# LM2596_Adjustable_AMS1117.net
KiCad netlist of a schematic drawn in Altium Designer
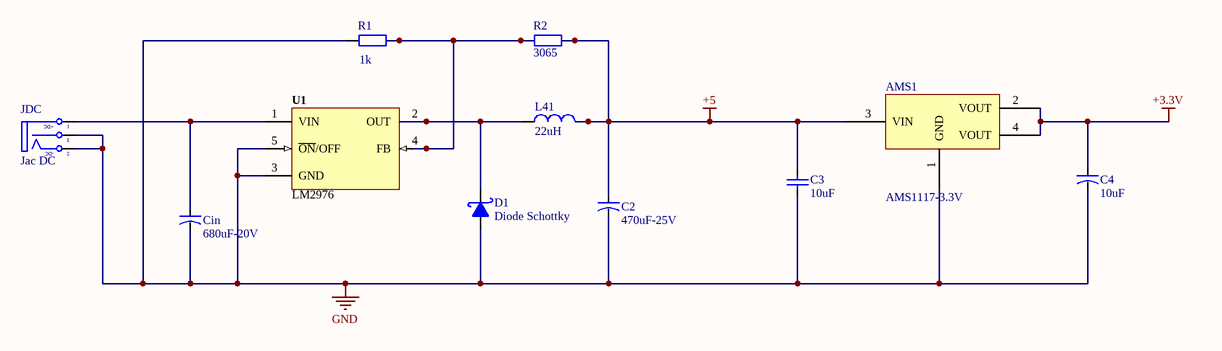
[diagram p0: LM2596 Adjustable_AMS1117.SchDoc]

(export (version "E")
  (design (tool "Eeschema 10.0.6"))
  (components
    (comp (ref "AMS1")
      (value "AMS1117-3.3V")
      (footprint "SOT223")
      (description "Dán")
      (libsource (lib "Altium_Lib_by_KhueNguyenCreator") (part "AMS1117 SMD"))
    )
    (comp (ref "C2")
      (value "470uF-25V")
      (footprint "CAP_D16")
      (description "Capacitor (Semiconductor SIM Model)")
      (fields (field (name "PUBLISHER") "Altium Limited"))
      (libsource (lib "My Library") (part "CAP-ALU-DIP"))
    )
    (comp (ref "C3")
      (value "10uF")
      (footprint "CAP_0805")
      (description "Capacitor")
      (fields (field (name "PUBLISHER") "Altium Limited"))
      (libsource (lib "My Library") (part "CapSMD"))
    )
    (comp (ref "C4")
      (value "10uF")
      (footprint "CAP_D16")
      (description "Capacitor (Semiconductor SIM Model)")
      (fields (field (name "PUBLISHER") "Altium Limited"))
      (libsource (lib "My Library") (part "CAP-ALU-DIP"))
    )
    (comp (ref "Cin")
      (value "680uF-20V")
      (footprint "CAP_D16")
      (description "Capacitor (Semiconductor SIM Model)")
      (fields (field (name "PUBLISHER") "Altium Limited"))
      (libsource (lib "My Library") (part "CAP-ALU-DIP"))
    )
    (comp (ref "D1")
      (value "Diode Schottky")
      (footprint "DIODE_ZENER_SMD")
      (description "Generic Diode Schottky")
      (libsource (lib "My Library") (part "Diode Schottky"))
    )
    (comp (ref "JDC")
      (value "Jac DC")
      (footprint "DC-IN")
      (description "Jac DC input")
      (libsource (lib "My Library") (part "DCIN"))
    )
    (comp (ref "L41")
      (value "22uH")
      (footprint "Inductor_SMD")
      (description "Inductor")
      (libsource (lib "My Library") (part "L1"))
    )
    (comp (ref "R1")
      (value "1k")
      (footprint "RES-SMD-0805")
      (description "Resistor SMD")
      (fields
        (field (name "MANUFACTURER") "Generic Components")
        (field (name "PUBLISHER") "Altium Hobart Technology Centre")
      )
      (libsource (lib "My Library") (part "Resistor - SMD"))
    )
    (comp (ref "R2")
      (value "3065")
      (footprint "RES_SMD_0805")
      (description "Resistor SMD")
      (fields
        (field (name "MANUFACTURER") "Generic Components")
        (field (name "PUBLISHER") "Altium Hobart Technology Centre")
      )
      (libsource (lib "My Library") (part "Resistor - SMD"))
    )
    (comp (ref "U1") (value "LM2976") (footprint "LM2576t") (libsource (lib "My Library") (part "LM2596")))
  )
  (nets
    (net (code "1") (name "+3.3V") (class "Default")
      (node (ref "AMS1") (pin "2") (pinfunction "VOUT_2") (pintype "passive"))
      (node (ref "AMS1") (pin "4") (pinfunction "VOUT_4") (pintype "passive"))
      (node (ref "C4") (pin "1") (pinfunction "1_1") (pintype "passive"))
    )
    (net (code "2") (name "+5") (class "Default")
      (node (ref "AMS1") (pin "3") (pinfunction "VIN_3") (pintype "passive"))
      (node (ref "C2") (pin "1") (pinfunction "1_1") (pintype "passive"))
      (node (ref "C3") (pin "2") (pinfunction "2_2") (pintype "passive"))
      (node (ref "L41") (pin "2") (pinfunction "2_2") (pintype "passive"))
      (node (ref "R2") (pin "1") (pinfunction "1_1") (pintype "passive"))
    )
    (net (code "3") (name "GND") (class "Default")
      (node (ref "AMS1") (pin "1") (pinfunction "GND_1") (pintype "passive"))
      (node (ref "C2") (pin "2") (pinfunction "2_2") (pintype "passive"))
      (node (ref "C3") (pin "1") (pinfunction "1_1") (pintype "passive"))
      (node (ref "C4") (pin "2") (pinfunction "2_2") (pintype "passive"))
      (node (ref "Cin") (pin "2") (pinfunction "2_2") (pintype "passive"))
      (node (ref "D1") (pin "1") (pinfunction "A_1") (pintype "passive"))
      (node (ref "JDC") (pin "2") (pinfunction "TN_2") (pintype "passive"))
      (node (ref "JDC") (pin "3") (pinfunction "S_3") (pintype "power_in"))
      (node (ref "R1") (pin "2") (pinfunction "2_2") (pintype "passive"))
      (node (ref "U1") (pin "3") (pinfunction "GND_3") (pintype "power_in"))
      (node (ref "U1") (pin "5") (pinfunction "~{ON}/OFF_5") (pintype "input"))
    )
    (net (code "4") (name "Net-(D1-K)") (class "Default")
      (node (ref "D1") (pin "2") (pinfunction "K_2") (pintype "passive"))
      (node (ref "L41") (pin "1") (pinfunction "1_1") (pintype "passive"))
      (node (ref "U1") (pin "2") (pinfunction "OUT_2") (pintype "power_in"))
    )
    (net (code "5") (name "Net-(JDC-T)") (class "Default")
      (node (ref "Cin") (pin "1") (pinfunction "1_1") (pintype "passive"))
      (node (ref "JDC") (pin "1") (pinfunction "T_1") (pintype "passive"))
      (node (ref "U1") (pin "1") (pinfunction "VIN_1") (pintype "power_in"))
    )
    (net (code "6") (name "Net-(U1-FB)") (class "Default")
      (node (ref "R1") (pin "1") (pinfunction "1_1") (pintype "passive"))
      (node (ref "R2") (pin "2") (pinfunction "2_2") (pintype "passive"))
      (node (ref "U1") (pin "4") (pinfunction "FB_4") (pintype "input"))
    )
  )
)
